# Dachmodul.net
KiCad netlist of a schematic drawn in EAGLE
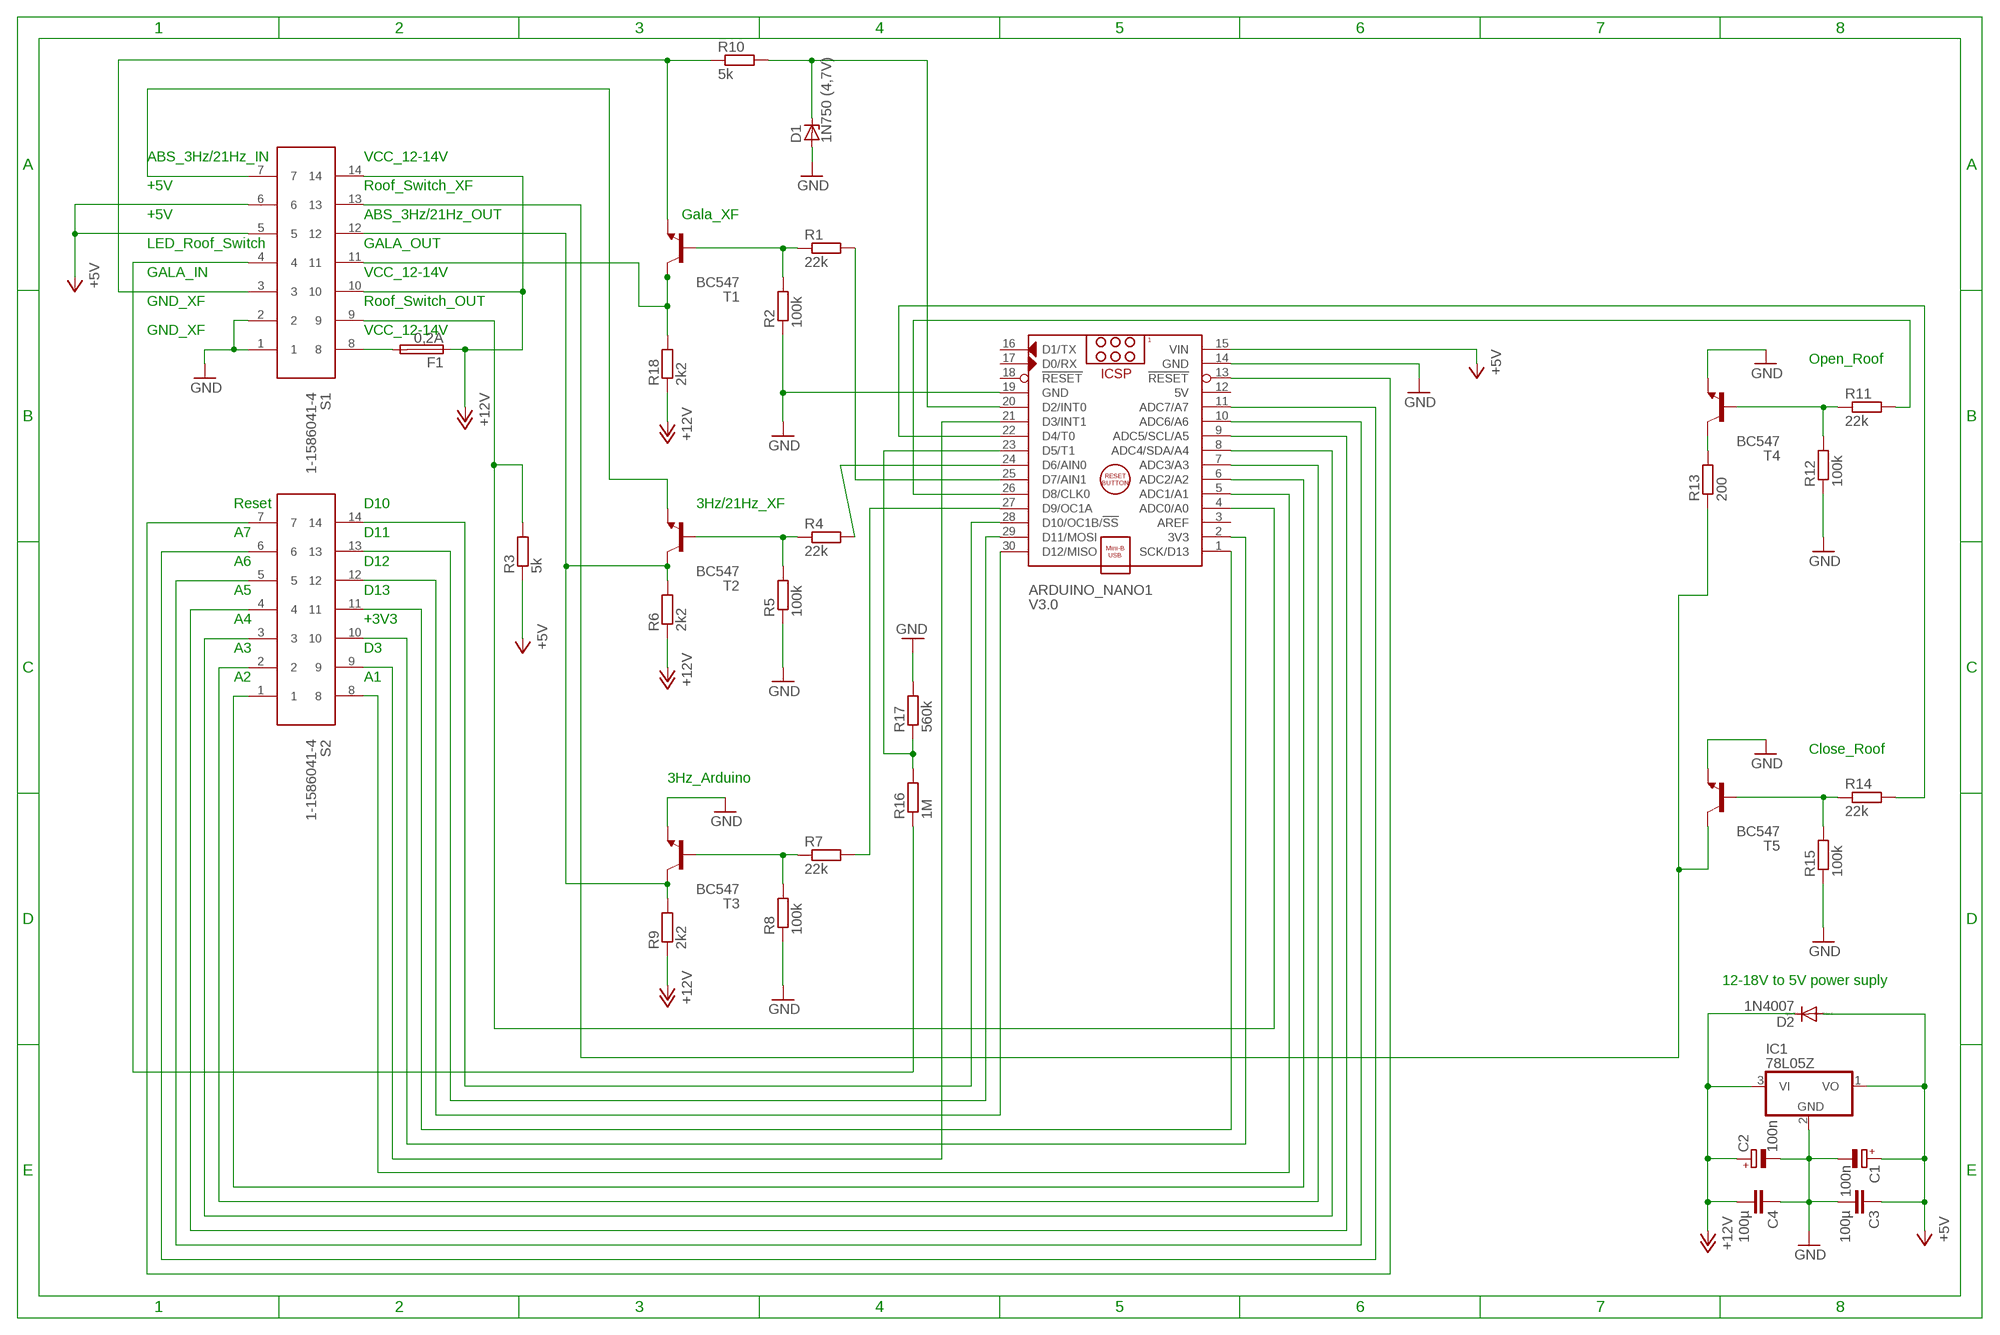
[diagram p0: schematic, sheet 1]

(export (version "E")
  (design (tool "Eeschema 10.0.6"))
  (components
    (comp (ref "ARDUINO_NANO1")
      (value "V3.0")
      (footprint "eagle-import:ARDUINO_NANO")
      (libsource (lib "eagle-import") (part "ARDUINO_NANO"))
    )
    (comp (ref "C1")
      (value "100n")
      (footprint "eagle-import:E3,5-8")
      (libsource (lib "eagle-import") (part "CPOL-EUE3.5-8"))
    )
    (comp (ref "C2")
      (value "100n")
      (footprint "eagle-import:E3,5-8")
      (libsource (lib "eagle-import") (part "CPOL-EUE3.5-8"))
    )
    (comp (ref "C3")
      (value "100µ")
      (footprint "eagle-import:C025-025X050")
      (libsource (lib "eagle-import") (part "C-EU025-025X050"))
    )
    (comp (ref "C4")
      (value "100µ")
      (footprint "eagle-import:C025-025X050")
      (libsource (lib "eagle-import") (part "C-EU025-025X050"))
    )
    (comp (ref "D1")
      (value "1N750 (4,7V)")
      (footprint "eagle-import:ZDIO-2.5")
      (libsource (lib "eagle-import") (part "ZENER-DIODEZD-2.5"))
    )
    (comp (ref "D2")
      (value "1N4007")
      (footprint "eagle-import:DO41-10")
      (libsource (lib "eagle-import") (part "1N4004"))
    )
    (comp (ref "F1")
      (value "0,2A")
      (footprint "eagle-import:GSH15")
      (fields (field (name "MPN") "64900001039"))
      (libsource (lib "eagle-import") (part "GSH15"))
    )
    (comp (ref "IC1")
      (value "78L05Z")
      (footprint "eagle-import:TO92")
      (libsource (lib "eagle-import") (part "78ZL05"))
    )
    (comp (ref "R1")
      (value "22k")
      (footprint "eagle-import:0204_5")
      (libsource (lib "eagle-import") (part "R-EU_0204/5"))
    )
    (comp (ref "R2")
      (value "100k")
      (footprint "eagle-import:0204_5")
      (libsource (lib "eagle-import") (part "R-EU_0204/5"))
    )
    (comp (ref "R3")
      (value "5k")
      (footprint "eagle-import:0204_5")
      (libsource (lib "eagle-import") (part "R-EU_0204/5"))
    )
    (comp (ref "R4")
      (value "22k")
      (footprint "eagle-import:0204_5")
      (libsource (lib "eagle-import") (part "R-EU_0204/5"))
    )
    (comp (ref "R5")
      (value "100k")
      (footprint "eagle-import:0204_5")
      (libsource (lib "eagle-import") (part "R-EU_0204/5"))
    )
    (comp (ref "R6")
      (value "2k2")
      (footprint "eagle-import:0204_5")
      (libsource (lib "eagle-import") (part "R-EU_0204/5"))
    )
    (comp (ref "R7")
      (value "22k")
      (footprint "eagle-import:0204_5")
      (libsource (lib "eagle-import") (part "R-EU_0204/5"))
    )
    (comp (ref "R8")
      (value "100k")
      (footprint "eagle-import:0204_5")
      (libsource (lib "eagle-import") (part "R-EU_0204/5"))
    )
    (comp (ref "R9")
      (value "2k2")
      (footprint "eagle-import:0204_5")
      (libsource (lib "eagle-import") (part "R-EU_0204/5"))
    )
    (comp (ref "R10")
      (value "5k")
      (footprint "eagle-import:0204_5")
      (libsource (lib "eagle-import") (part "R-EU_0204/5"))
    )
    (comp (ref "R11")
      (value "22k")
      (footprint "eagle-import:0204_5")
      (libsource (lib "eagle-import") (part "R-EU_0204/5"))
    )
    (comp (ref "R12")
      (value "100k")
      (footprint "eagle-import:0204_5")
      (libsource (lib "eagle-import") (part "R-EU_0204/5"))
    )
    (comp (ref "R13")
      (value "200")
      (footprint "eagle-import:0204_5")
      (libsource (lib "eagle-import") (part "R-EU_0204/5"))
    )
    (comp (ref "R14")
      (value "22k")
      (footprint "eagle-import:0204_5")
      (libsource (lib "eagle-import") (part "R-EU_0204/5"))
    )
    (comp (ref "R15")
      (value "100k")
      (footprint "eagle-import:0204_5")
      (libsource (lib "eagle-import") (part "R-EU_0204/5"))
    )
    (comp (ref "R16")
      (value "1M")
      (footprint "eagle-import:0204_5")
      (libsource (lib "eagle-import") (part "R-EU_0204/5"))
    )
    (comp (ref "R17")
      (value "560k")
      (footprint "eagle-import:0204_5")
      (libsource (lib "eagle-import") (part "R-EU_0204/5"))
    )
    (comp (ref "R18")
      (value "2k2")
      (footprint "eagle-import:0204V")
      (libsource (lib "eagle-import") (part "rcl_334_R-EU_0204/2V"))
    )
    (comp (ref "S1")
      (value "1-1586041-4")
      (footprint "eagle-import:64901421022")
      (libsource (lib "eagle-import") (part "64901421022"))
    )
    (comp (ref "S2")
      (value "1-1586041-4")
      (footprint "eagle-import:64901421022")
      (libsource (lib "eagle-import") (part "64901421022"))
    )
    (comp (ref "T1")
      (value "BC547")
      (footprint "eagle-import:TO92")
      (libsource (lib "eagle-import") (part "BC547"))
    )
    (comp (ref "T2")
      (value "BC547")
      (footprint "eagle-import:TO92")
      (libsource (lib "eagle-import") (part "BC547"))
    )
    (comp (ref "T3")
      (value "BC547")
      (footprint "eagle-import:TO92")
      (libsource (lib "eagle-import") (part "BC547"))
    )
    (comp (ref "T4")
      (value "BC547")
      (footprint "eagle-import:TO92")
      (libsource (lib "eagle-import") (part "BC547"))
    )
    (comp (ref "T5")
      (value "BC547")
      (footprint "eagle-import:TO92")
      (libsource (lib "eagle-import") (part "BC547"))
    )
  )
  (nets
    (net (code "1") (name "+5V") (class "Default")
      (node (ref "ARDUINO_NANO1") (pin "15") (pinfunction "VIN_15") (pintype "power_in"))
      (node (ref "C1") (pin "+") (pinfunction "+_+") (pintype "passive"))
      (node (ref "C3") (pin "1") (pinfunction "1_1") (pintype "passive"))
      (node (ref "D2") (pin "A") (pinfunction "A_A") (pintype "passive"))
      (node (ref "IC1") (pin "1") (pinfunction "VO_1") (pintype "passive"))
      (node (ref "R3") (pin "1") (pinfunction "1_1") (pintype "passive"))
      (node (ref "S1") (pin "5") (pinfunction "5_5") (pintype "bidirectional"))
      (node (ref "S1") (pin "6") (pinfunction "6_6") (pintype "bidirectional"))
    )
    (net (code "2") (name "+12V") (class "Default")
      (node (ref "C2") (pin "+") (pinfunction "+_+") (pintype "passive"))
      (node (ref "C4") (pin "2") (pinfunction "2_2") (pintype "passive"))
      (node (ref "D2") (pin "C") (pinfunction "C_C") (pintype "passive"))
      (node (ref "F1") (pin "1") (pinfunction "1_1") (pintype "passive"))
      (node (ref "IC1") (pin "3") (pinfunction "VI_3") (pintype "input"))
      (node (ref "R18") (pin "1") (pinfunction "1_1") (pintype "passive"))
      (node (ref "R6") (pin "1") (pinfunction "1_1") (pintype "passive"))
      (node (ref "R9") (pin "1") (pinfunction "1_1") (pintype "passive"))
      (node (ref "S1") (pin "10") (pinfunction "10_10") (pintype "bidirectional"))
      (node (ref "S1") (pin "14") (pinfunction "14_14") (pintype "bidirectional"))
    )
    (net (code "3") (name "/5V") (class "Default")
      (node (ref "ARDUINO_NANO1") (pin "12") (pinfunction "5V_12") (pintype "power_in"))
    )
    (net (code "4") (name "GND") (class "Default")
      (node (ref "ARDUINO_NANO1") (pin "14") (pinfunction "GND_14") (pintype "power_in"))
      (node (ref "ARDUINO_NANO1") (pin "19") (pinfunction "GND_19") (pintype "power_in"))
      (node (ref "C1") (pin "-") (pinfunction "-_-") (pintype "passive"))
      (node (ref "C2") (pin "-") (pinfunction "-_-") (pintype "passive"))
      (node (ref "C3") (pin "2") (pinfunction "2_2") (pintype "passive"))
      (node (ref "C4") (pin "1") (pinfunction "1_1") (pintype "passive"))
      (node (ref "D1") (pin "A") (pinfunction "A_A") (pintype "passive"))
      (node (ref "IC1") (pin "2") (pinfunction "GND_2") (pintype "passive"))
      (node (ref "R12") (pin "1") (pinfunction "1_1") (pintype "passive"))
      (node (ref "R15") (pin "1") (pinfunction "1_1") (pintype "passive"))
      (node (ref "R17") (pin "2") (pinfunction "2_2") (pintype "passive"))
      (node (ref "R2") (pin "1") (pinfunction "1_1") (pintype "passive"))
      (node (ref "R5") (pin "1") (pinfunction "1_1") (pintype "passive"))
      (node (ref "R8") (pin "1") (pinfunction "1_1") (pintype "passive"))
      (node (ref "S1") (pin "1") (pinfunction "1_1") (pintype "bidirectional"))
      (node (ref "S1") (pin "2") (pinfunction "2_2") (pintype "bidirectional"))
      (node (ref "T3") (pin "1") (pinfunction "E_1") (pintype "passive"))
      (node (ref "T4") (pin "1") (pinfunction "E_1") (pintype "passive"))
      (node (ref "T5") (pin "1") (pinfunction "E_1") (pintype "passive"))
    )
    (net (code "5") (name "Net-(ARDUINO_NANO1-3V3)") (class "Default")
      (node (ref "ARDUINO_NANO1") (pin "2") (pinfunction "3V3_2") (pintype "output"))
      (node (ref "S2") (pin "10") (pinfunction "10_10") (pintype "bidirectional"))
    )
    (net (code "6") (name "Net-(ARDUINO_NANO1-ADC0{slash}A0)") (class "Default")
      (node (ref "ARDUINO_NANO1") (pin "4") (pinfunction "ADC0/A0_4") (pintype "bidirectional"))
      (node (ref "R3") (pin "2") (pinfunction "2_2") (pintype "passive"))
      (node (ref "S1") (pin "9") (pinfunction "9_9") (pintype "bidirectional"))
    )
    (net (code "7") (name "Net-(ARDUINO_NANO1-ADC1{slash}A1)") (class "Default")
      (node (ref "ARDUINO_NANO1") (pin "5") (pinfunction "ADC1/A1_5") (pintype "bidirectional"))
      (node (ref "S2") (pin "8") (pinfunction "8_8") (pintype "bidirectional"))
    )
    (net (code "8") (name "Net-(ARDUINO_NANO1-ADC2{slash}A2)") (class "Default")
      (node (ref "ARDUINO_NANO1") (pin "6") (pinfunction "ADC2/A2_6") (pintype "bidirectional"))
      (node (ref "S2") (pin "1") (pinfunction "1_1") (pintype "bidirectional"))
    )
    (net (code "9") (name "Net-(ARDUINO_NANO1-ADC3{slash}A3)") (class "Default")
      (node (ref "ARDUINO_NANO1") (pin "7") (pinfunction "ADC3/A3_7") (pintype "bidirectional"))
      (node (ref "S2") (pin "2") (pinfunction "2_2") (pintype "bidirectional"))
    )
    (net (code "10") (name "Net-(ARDUINO_NANO1-ADC4{slash}SDA{slash}A4)") (class "Default")
      (node (ref "ARDUINO_NANO1") (pin "8") (pinfunction "ADC4/SDA/A4_8") (pintype "bidirectional"))
      (node (ref "S2") (pin "3") (pinfunction "3_3") (pintype "bidirectional"))
    )
    (net (code "11") (name "Net-(ARDUINO_NANO1-ADC5{slash}SCL{slash}A5)") (class "Default")
      (node (ref "ARDUINO_NANO1") (pin "9") (pinfunction "ADC5/SCL/A5_9") (pintype "bidirectional"))
      (node (ref "S2") (pin "4") (pinfunction "4_4") (pintype "bidirectional"))
    )
    (net (code "12") (name "Net-(ARDUINO_NANO1-ADC6{slash}A6)") (class "Default")
      (node (ref "ARDUINO_NANO1") (pin "10") (pinfunction "ADC6/A6_10") (pintype "bidirectional"))
      (node (ref "S2") (pin "5") (pinfunction "5_5") (pintype "bidirectional"))
    )
    (net (code "13") (name "Net-(ARDUINO_NANO1-ADC7{slash}A7)") (class "Default")
      (node (ref "ARDUINO_NANO1") (pin "11") (pinfunction "ADC7/A7_11") (pintype "bidirectional"))
      (node (ref "S2") (pin "6") (pinfunction "6_6") (pintype "bidirectional"))
    )
    (net (code "14") (name "Net-(ARDUINO_NANO1-D2{slash}INT0)") (class "Default")
      (node (ref "ARDUINO_NANO1") (pin "20") (pinfunction "D2/INT0_20") (pintype "bidirectional"))
      (node (ref "D1") (pin "C") (pinfunction "C_C") (pintype "passive"))
      (node (ref "R10") (pin "2") (pinfunction "2_2") (pintype "passive"))
    )
    (net (code "15") (name "Net-(ARDUINO_NANO1-D3{slash}INT1)") (class "Default")
      (node (ref "ARDUINO_NANO1") (pin "21") (pinfunction "D3/INT1_21") (pintype "bidirectional"))
      (node (ref "S2") (pin "9") (pinfunction "9_9") (pintype "bidirectional"))
    )
    (net (code "16") (name "Net-(ARDUINO_NANO1-D4{slash}T0)") (class "Default")
      (node (ref "ARDUINO_NANO1") (pin "22") (pinfunction "D4/T0_22") (pintype "bidirectional"))
      (node (ref "R14") (pin "2") (pinfunction "2_2") (pintype "passive"))
    )
    (net (code "17") (name "Net-(ARDUINO_NANO1-D5{slash}T1)") (class "Default")
      (node (ref "ARDUINO_NANO1") (pin "23") (pinfunction "D5/T1_23") (pintype "bidirectional"))
      (node (ref "R16") (pin "2") (pinfunction "2_2") (pintype "passive"))
      (node (ref "R17") (pin "1") (pinfunction "1_1") (pintype "passive"))
    )
    (net (code "18") (name "Net-(ARDUINO_NANO1-D6{slash}AIN0)") (class "Default")
      (node (ref "ARDUINO_NANO1") (pin "24") (pinfunction "D6/AIN0_24") (pintype "bidirectional"))
      (node (ref "R4") (pin "2") (pinfunction "2_2") (pintype "passive"))
    )
    (net (code "19") (name "Net-(ARDUINO_NANO1-D7{slash}AIN1)") (class "Default")
      (node (ref "ARDUINO_NANO1") (pin "25") (pinfunction "D7/AIN1_25") (pintype "bidirectional"))
      (node (ref "R1") (pin "2") (pinfunction "2_2") (pintype "passive"))
    )
    (net (code "20") (name "Net-(ARDUINO_NANO1-D8{slash}CLK0)") (class "Default")
      (node (ref "ARDUINO_NANO1") (pin "26") (pinfunction "D8/CLK0_26") (pintype "bidirectional"))
      (node (ref "R11") (pin "2") (pinfunction "2_2") (pintype "passive"))
    )
    (net (code "21") (name "Net-(ARDUINO_NANO1-D9{slash}OC1A)") (class "Default")
      (node (ref "ARDUINO_NANO1") (pin "27") (pinfunction "D9/OC1A_27") (pintype "bidirectional"))
      (node (ref "R7") (pin "2") (pinfunction "2_2") (pintype "passive"))
    )
    (net (code "22") (name "Net-(ARDUINO_NANO1-D10{slash}OC1B{slash}~{SS})") (class "Default")
      (node (ref "ARDUINO_NANO1") (pin "28") (pinfunction "D10/OC1B/~{SS}_28") (pintype "bidirectional"))
      (node (ref "S2") (pin "14") (pinfunction "14_14") (pintype "bidirectional"))
    )
    (net (code "23") (name "Net-(ARDUINO_NANO1-D11{slash}MOSI)") (class "Default")
      (node (ref "ARDUINO_NANO1") (pin "29") (pinfunction "D11/MOSI_29") (pintype "bidirectional"))
      (node (ref "S2") (pin "13") (pinfunction "13_13") (pintype "bidirectional"))
    )
    (net (code "24") (name "Net-(ARDUINO_NANO1-D12{slash}MISO)") (class "Default")
      (node (ref "ARDUINO_NANO1") (pin "30") (pinfunction "D12/MISO_30") (pintype "bidirectional"))
      (node (ref "S2") (pin "12") (pinfunction "12_12") (pintype "bidirectional"))
    )
    (net (code "25") (name "Net-(ARDUINO_NANO1-SCK{slash}D13)") (class "Default")
      (node (ref "ARDUINO_NANO1") (pin "1") (pinfunction "SCK/D13_1") (pintype "bidirectional"))
      (node (ref "S2") (pin "11") (pinfunction "11_11") (pintype "bidirectional"))
    )
    (net (code "26") (name "Net-(ARDUINO_NANO1-~{RESET}-Pad13)") (class "Default")
      (node (ref "ARDUINO_NANO1") (pin "13") (pinfunction "~{RESET}_13") (pintype "input"))
      (node (ref "S2") (pin "7") (pinfunction "7_7") (pintype "bidirectional"))
    )
    (net (code "27") (name "Net-(F1-Pad2)") (class "Default")
      (node (ref "F1") (pin "2") (pinfunction "2_2") (pintype "passive"))
      (node (ref "S1") (pin "8") (pinfunction "8_8") (pintype "bidirectional"))
    )
    (net (code "28") (name "Net-(R16-Pad1)") (class "Default")
      (node (ref "R16") (pin "1") (pinfunction "1_1") (pintype "passive"))
      (node (ref "S1") (pin "4") (pinfunction "4_4") (pintype "bidirectional"))
    )
    (net (code "29") (name "Net-(T1-B)") (class "Default")
      (node (ref "R1") (pin "1") (pinfunction "1_1") (pintype "passive"))
      (node (ref "R2") (pin "2") (pinfunction "2_2") (pintype "passive"))
      (node (ref "T1") (pin "2") (pinfunction "B_2") (pintype "passive"))
    )
    (net (code "30") (name "Net-(T1-C)") (class "Default")
      (node (ref "R18") (pin "2") (pinfunction "2_2") (pintype "passive"))
      (node (ref "S1") (pin "11") (pinfunction "11_11") (pintype "bidirectional"))
      (node (ref "T1") (pin "3") (pinfunction "C_3") (pintype "passive"))
    )
    (net (code "31") (name "Net-(T1-E)") (class "Default")
      (node (ref "R10") (pin "1") (pinfunction "1_1") (pintype "passive"))
      (node (ref "S1") (pin "3") (pinfunction "3_3") (pintype "bidirectional"))
      (node (ref "T1") (pin "1") (pinfunction "E_1") (pintype "passive"))
    )
    (net (code "32") (name "Net-(T2-B)") (class "Default")
      (node (ref "R4") (pin "1") (pinfunction "1_1") (pintype "passive"))
      (node (ref "R5") (pin "2") (pinfunction "2_2") (pintype "passive"))
      (node (ref "T2") (pin "2") (pinfunction "B_2") (pintype "passive"))
    )
    (net (code "33") (name "Net-(T2-C)") (class "Default")
      (node (ref "R6") (pin "2") (pinfunction "2_2") (pintype "passive"))
      (node (ref "R9") (pin "2") (pinfunction "2_2") (pintype "passive"))
      (node (ref "S1") (pin "12") (pinfunction "12_12") (pintype "bidirectional"))
      (node (ref "T2") (pin "3") (pinfunction "C_3") (pintype "passive"))
      (node (ref "T3") (pin "3") (pinfunction "C_3") (pintype "passive"))
    )
    (net (code "34") (name "Net-(T2-E)") (class "Default")
      (node (ref "S1") (pin "7") (pinfunction "7_7") (pintype "bidirectional"))
      (node (ref "T2") (pin "1") (pinfunction "E_1") (pintype "passive"))
    )
    (net (code "35") (name "Net-(T3-B)") (class "Default")
      (node (ref "R7") (pin "1") (pinfunction "1_1") (pintype "passive"))
      (node (ref "R8") (pin "2") (pinfunction "2_2") (pintype "passive"))
      (node (ref "T3") (pin "2") (pinfunction "B_2") (pintype "passive"))
    )
    (net (code "36") (name "Net-(T4-B)") (class "Default")
      (node (ref "R11") (pin "1") (pinfunction "1_1") (pintype "passive"))
      (node (ref "R12") (pin "2") (pinfunction "2_2") (pintype "passive"))
      (node (ref "T4") (pin "2") (pinfunction "B_2") (pintype "passive"))
    )
    (net (code "37") (name "Net-(T4-C)") (class "Default")
      (node (ref "R13") (pin "2") (pinfunction "2_2") (pintype "passive"))
      (node (ref "T4") (pin "3") (pinfunction "C_3") (pintype "passive"))
    )
    (net (code "38") (name "Net-(T5-B)") (class "Default")
      (node (ref "R14") (pin "1") (pinfunction "1_1") (pintype "passive"))
      (node (ref "R15") (pin "2") (pinfunction "2_2") (pintype "passive"))
      (node (ref "T5") (pin "2") (pinfunction "B_2") (pintype "passive"))
    )
    (net (code "39") (name "Net-(T5-C)") (class "Default")
      (node (ref "R13") (pin "1") (pinfunction "1_1") (pintype "passive"))
      (node (ref "S1") (pin "13") (pinfunction "13_13") (pintype "bidirectional"))
      (node (ref "T5") (pin "3") (pinfunction "C_3") (pintype "passive"))
    )
    (net (code "40") (name "unconnected-(ARDUINO_NANO1-AREF-Pad3)") (class "Default")
      (node (ref "ARDUINO_NANO1") (pin "3") (pinfunction "AREF_3") (pintype "input"))
    )
    (net (code "41") (name "unconnected-(ARDUINO_NANO1-D0{slash}RX-Pad17)") (class "Default")
      (node (ref "ARDUINO_NANO1") (pin "17") (pinfunction "D0/RX_17") (pintype "bidirectional"))
    )
    (net (code "42") (name "unconnected-(ARDUINO_NANO1-D1{slash}TX-Pad16)") (class "Default")
      (node (ref "ARDUINO_NANO1") (pin "16") (pinfunction "D1/TX_16") (pintype "bidirectional"))
    )
    (net (code "43") (name "unconnected-(ARDUINO_NANO1-~{RESET}-Pad18)") (class "Default")
      (node (ref "ARDUINO_NANO1") (pin "18") (pinfunction "~{RESET}_18") (pintype "input"))
    )
  )
)
